# sd1_redraw.net
KiCad netlist of a schematic drawn in EAGLE
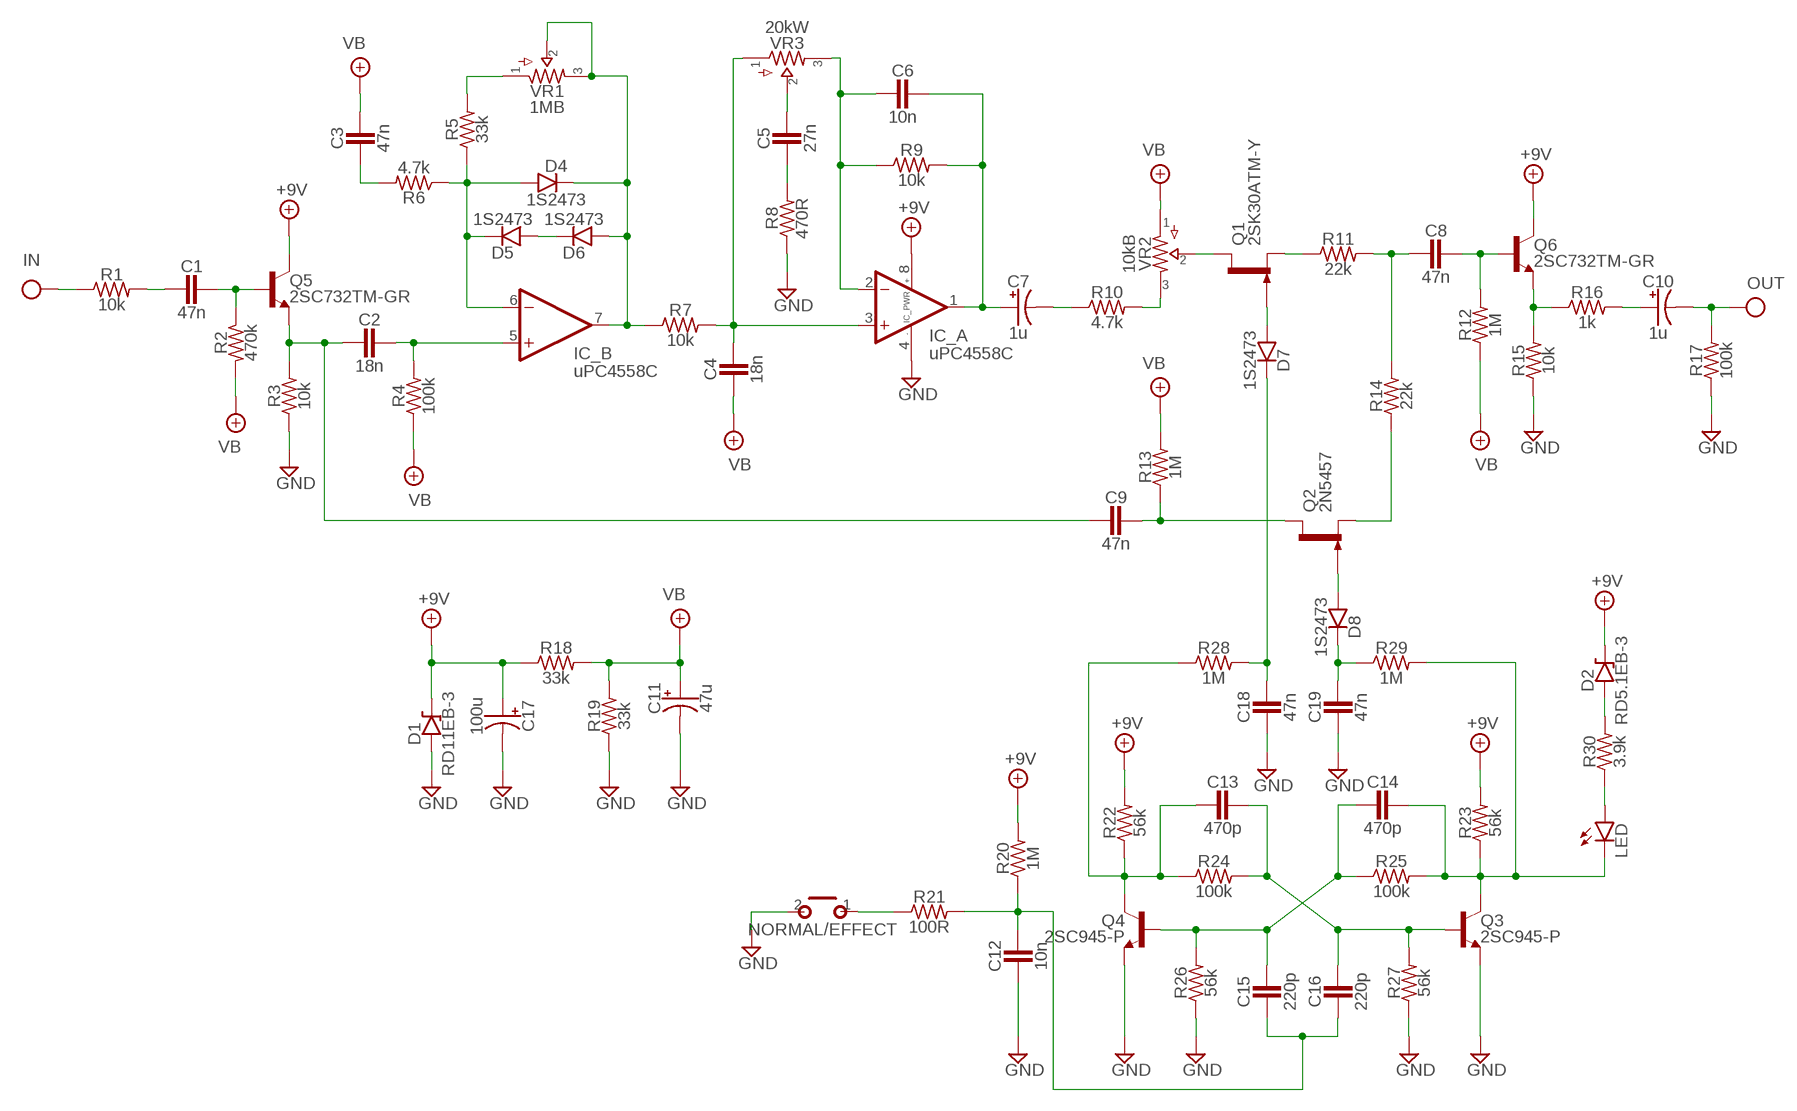
[diagram p0: schematic, sheet 1]

(export (version "E")
  (design (tool "Eeschema 10.0.6"))
  (components
    (comp (ref "C1")
      (value "47n")
      (footprint "eagle-import:BOX_SMALL")
      (libsource (lib "eagle-import") (part "CER/FILMBOX.1"))
    )
    (comp (ref "C2")
      (value "18n")
      (footprint "eagle-import:BOX_SMALL")
      (libsource (lib "eagle-import") (part "CER/FILMBOX.1"))
    )
    (comp (ref "C3")
      (value "47n")
      (footprint "eagle-import:BOX_SMALL")
      (libsource (lib "eagle-import") (part "CER/FILMBOX.1"))
    )
    (comp (ref "C4")
      (value "18n")
      (footprint "eagle-import:BOX_SMALL")
      (libsource (lib "eagle-import") (part "CER/FILMBOX.1"))
    )
    (comp (ref "C5")
      (value "27n")
      (footprint "eagle-import:BOX_SMALL")
      (libsource (lib "eagle-import") (part "CER/FILMBOX.1"))
    )
    (comp (ref "C6")
      (value "10n")
      (footprint "eagle-import:BOX_SMALL")
      (libsource (lib "eagle-import") (part "CER/FILMBOX.1"))
    )
    (comp (ref "C7")
      (value "1u")
      (footprint "eagle-import:040_020")
      (libsource (lib "eagle-import") (part "0400"))
    )
    (comp (ref "C8")
      (value "47n")
      (footprint "eagle-import:BOX_SMALL")
      (libsource (lib "eagle-import") (part "CER/FILMBOX.1"))
    )
    (comp (ref "C9")
      (value "47n")
      (footprint "eagle-import:BOX_SMALL")
      (libsource (lib "eagle-import") (part "CER/FILMBOX.1"))
    )
    (comp (ref "C10")
      (value "1u")
      (footprint "eagle-import:040_020")
      (libsource (lib "eagle-import") (part "0400"))
    )
    (comp (ref "C11")
      (value "47u")
      (footprint "eagle-import:040_020")
      (libsource (lib "eagle-import") (part "0400"))
    )
    (comp (ref "C12")
      (value "10n")
      (footprint "eagle-import:BOX_SMALL")
      (libsource (lib "eagle-import") (part "CER/FILMBOX.1"))
    )
    (comp (ref "C13")
      (value "470p")
      (footprint "eagle-import:BOX_SMALL")
      (libsource (lib "eagle-import") (part "CER/FILMBOX.1"))
    )
    (comp (ref "C14")
      (value "470p")
      (footprint "eagle-import:BOX_SMALL")
      (libsource (lib "eagle-import") (part "CER/FILMBOX.1"))
    )
    (comp (ref "C15")
      (value "220p")
      (footprint "eagle-import:BOX_SMALL")
      (libsource (lib "eagle-import") (part "CER/FILMBOX.1"))
    )
    (comp (ref "C16")
      (value "220p")
      (footprint "eagle-import:BOX_SMALL")
      (libsource (lib "eagle-import") (part "CER/FILMBOX.1"))
    )
    (comp (ref "C17")
      (value "100u")
      (footprint "eagle-import:040_020")
      (libsource (lib "eagle-import") (part "0400"))
    )
    (comp (ref "C18")
      (value "47n")
      (footprint "eagle-import:BOX_SMALL")
      (libsource (lib "eagle-import") (part "CER/FILMBOX.1"))
    )
    (comp (ref "C19")
      (value "47n")
      (footprint "eagle-import:BOX_SMALL")
      (libsource (lib "eagle-import") (part "CER/FILMBOX.1"))
    )
    (comp (ref "D1")
      (value "RD11EB-3")
      (footprint "eagle-import:DO41-2")
      (libsource (lib "eagle-import") (part "ZENER.2"))
    )
    (comp (ref "D2")
      (value "RD5.1EB-3")
      (footprint "eagle-import:DO41-2")
      (libsource (lib "eagle-import") (part "ZENER.2"))
    )
    (comp (ref "D4")
      (value "1S2473")
      (footprint "eagle-import:DO35-2")
      (libsource (lib "eagle-import") (part "DO35.2"))
    )
    (comp (ref "D5")
      (value "1S2473")
      (footprint "eagle-import:DO35-2")
      (libsource (lib "eagle-import") (part "DO35.2"))
    )
    (comp (ref "D6")
      (value "1S2473")
      (footprint "eagle-import:DO35-2")
      (libsource (lib "eagle-import") (part "DO35.2"))
    )
    (comp (ref "D7")
      (value "1S2473")
      (footprint "eagle-import:DO35-2")
      (libsource (lib "eagle-import") (part "DO35.2"))
    )
    (comp (ref "D8")
      (value "1S2473")
      (footprint "eagle-import:DO35-2")
      (libsource (lib "eagle-import") (part "DO35.2"))
    )
    (comp (ref "IC")
      (value "uPC4558C")
      (footprint "eagle-import:DIL0")
      (libsource (lib "eagle-import") (part "DUALTH"))
    )
    (comp (ref "LED")
      (value "SLP1358")
      (footprint "eagle-import:3MM_D")
      (libsource (lib "eagle-import") (part "LED"))
    )
    (comp (ref "NORMAL/EFFECT")
      (value "MOMENTARY")
      (footprint "eagle-import:SPST")
      (libsource (lib "eagle-import") (part "MOMENTARY"))
    )
    (comp (ref "Q1")
      (value "2SK30ATM-Y")
      (footprint "eagle-import:TO92-")
      (libsource (lib "eagle-import") (part "2N5457"))
    )
    (comp (ref "Q2")
      (value "2N5457")
      (footprint "eagle-import:TO92-")
      (libsource (lib "eagle-import") (part "2N5457"))
    )
    (comp (ref "Q3")
      (value "2SC945-P")
      (footprint "eagle-import:TO92-")
      (libsource (lib "eagle-import") (part "2SC828A"))
    )
    (comp (ref "Q4")
      (value "2SC945-P")
      (footprint "eagle-import:TO92-")
      (libsource (lib "eagle-import") (part "2SC828A"))
    )
    (comp (ref "Q5")
      (value "2SC732TM-GR")
      (footprint "eagle-import:TO92-")
      (libsource (lib "eagle-import") (part "2SC828A"))
    )
    (comp (ref "Q6")
      (value "2SC732TM-GR")
      (footprint "eagle-import:TO92-")
      (libsource (lib "eagle-import") (part "2SC828A"))
    )
    (comp (ref "R1")
      (value "10k")
      (footprint "eagle-import:R0207_3")
      (libsource (lib "eagle-import") (part "R_.3B"))
    )
    (comp (ref "R2")
      (value "470k")
      (footprint "eagle-import:R0207_3")
      (libsource (lib "eagle-import") (part "R_.3B"))
    )
    (comp (ref "R3")
      (value "10k")
      (footprint "eagle-import:R0207_3")
      (libsource (lib "eagle-import") (part "R_.3B"))
    )
    (comp (ref "R4")
      (value "100k")
      (footprint "eagle-import:R0207_3")
      (libsource (lib "eagle-import") (part "R_.3B"))
    )
    (comp (ref "R5")
      (value "33k")
      (footprint "eagle-import:R0207_3")
      (libsource (lib "eagle-import") (part "R_.3B"))
    )
    (comp (ref "R6")
      (value "4.7k")
      (footprint "eagle-import:R0207_3")
      (libsource (lib "eagle-import") (part "R_.3B"))
    )
    (comp (ref "R7")
      (value "10k")
      (footprint "eagle-import:R0207_3")
      (libsource (lib "eagle-import") (part "R_.3B"))
    )
    (comp (ref "R8")
      (value "470R")
      (footprint "eagle-import:R0207_3")
      (libsource (lib "eagle-import") (part "R_.3B"))
    )
    (comp (ref "R9")
      (value "10k")
      (footprint "eagle-import:R0207_3")
      (libsource (lib "eagle-import") (part "R_.3B"))
    )
    (comp (ref "R10")
      (value "4.7k")
      (footprint "eagle-import:R0207_3")
      (libsource (lib "eagle-import") (part "R_.3B"))
    )
    (comp (ref "R11")
      (value "22k")
      (footprint "eagle-import:R0207_3")
      (libsource (lib "eagle-import") (part "R_.3B"))
    )
    (comp (ref "R12")
      (value "1M")
      (footprint "eagle-import:R0207_3")
      (libsource (lib "eagle-import") (part "R_.3B"))
    )
    (comp (ref "R13")
      (value "1M")
      (footprint "eagle-import:R0207_3")
      (libsource (lib "eagle-import") (part "R_.3B"))
    )
    (comp (ref "R14")
      (value "22k")
      (footprint "eagle-import:R0207_3")
      (libsource (lib "eagle-import") (part "R_.3B"))
    )
    (comp (ref "R15")
      (value "10k")
      (footprint "eagle-import:R0207_3")
      (libsource (lib "eagle-import") (part "R_.3B"))
    )
    (comp (ref "R16")
      (value "1k")
      (footprint "eagle-import:R0207_3")
      (libsource (lib "eagle-import") (part "R_.3B"))
    )
    (comp (ref "R17")
      (value "100k")
      (footprint "eagle-import:R0207_3")
      (libsource (lib "eagle-import") (part "R_.3B"))
    )
    (comp (ref "R18")
      (value "33k")
      (footprint "eagle-import:R0207_3")
      (libsource (lib "eagle-import") (part "R_.3B"))
    )
    (comp (ref "R19")
      (value "33k")
      (footprint "eagle-import:R0207_3")
      (libsource (lib "eagle-import") (part "R_.3B"))
    )
    (comp (ref "R20")
      (value "1M")
      (footprint "eagle-import:R0207_3")
      (libsource (lib "eagle-import") (part "R_.3B"))
    )
    (comp (ref "R21")
      (value "100R")
      (footprint "eagle-import:R0207_3")
      (libsource (lib "eagle-import") (part "R_.3B"))
    )
    (comp (ref "R22")
      (value "56k")
      (footprint "eagle-import:R0207_3")
      (libsource (lib "eagle-import") (part "R_.3B"))
    )
    (comp (ref "R23")
      (value "56k")
      (footprint "eagle-import:R0207_3")
      (libsource (lib "eagle-import") (part "R_.3B"))
    )
    (comp (ref "R24")
      (value "100k")
      (footprint "eagle-import:R0207_3")
      (libsource (lib "eagle-import") (part "R_.3B"))
    )
    (comp (ref "R25")
      (value "100k")
      (footprint "eagle-import:R0207_3")
      (libsource (lib "eagle-import") (part "R_.3B"))
    )
    (comp (ref "R26")
      (value "56k")
      (footprint "eagle-import:R0207_3")
      (libsource (lib "eagle-import") (part "R_.3B"))
    )
    (comp (ref "R27")
      (value "56k")
      (footprint "eagle-import:R0207_3")
      (libsource (lib "eagle-import") (part "R_.3B"))
    )
    (comp (ref "R28")
      (value "1M")
      (footprint "eagle-import:R0207_3")
      (libsource (lib "eagle-import") (part "R_.3B"))
    )
    (comp (ref "R29")
      (value "1M")
      (footprint "eagle-import:R0207_3")
      (libsource (lib "eagle-import") (part "R_.3B"))
    )
    (comp (ref "R30")
      (value "3.9k")
      (footprint "eagle-import:R0207_3")
      (libsource (lib "eagle-import") (part "R_.3B"))
    )
    (comp (ref "VR1")
      (value "1MB")
      (footprint "eagle-import:16MM")
      (libsource (lib "eagle-import") (part "POTS16MM"))
    )
    (comp (ref "VR2")
      (value "10kB")
      (footprint "eagle-import:16MM")
      (libsource (lib "eagle-import") (part "POTS16MM"))
    )
    (comp (ref "VR3")
      (value "20kW")
      (footprint "eagle-import:16MM")
      (libsource (lib "eagle-import") (part "POTS16MM"))
    )
  )
  (nets
    (net (code "1") (name "+9V") (class "Default")
      (node (ref "C17") (pin "+") (pinfunction "+_+") (pintype "passive"))
      (node (ref "D1") (pin "C") (pinfunction "C_C") (pintype "passive"))
      (node (ref "D2") (pin "C") (pinfunction "C_C") (pintype "passive"))
      (node (ref "IC") (pin "8") (pinfunction "V+_8") (pintype "power_in"))
      (node (ref "Q5") (pin "2") (pinfunction "C_2") (pintype "passive"))
      (node (ref "Q6") (pin "2") (pinfunction "C_2") (pintype "passive"))
      (node (ref "R18") (pin "1") (pinfunction "1_1") (pintype "passive"))
      (node (ref "R20") (pin "2") (pinfunction "2_2") (pintype "passive"))
      (node (ref "R22") (pin "2") (pinfunction "2_2") (pintype "passive"))
      (node (ref "R23") (pin "2") (pinfunction "2_2") (pintype "passive"))
    )
    (net (code "2") (name "GND") (class "Default")
      (node (ref "C11") (pin "-") (pinfunction "-_-") (pintype "passive"))
      (node (ref "C12") (pin "2") (pinfunction "2_2") (pintype "passive"))
      (node (ref "C17") (pin "-") (pinfunction "-_-") (pintype "passive"))
      (node (ref "C18") (pin "2") (pinfunction "2_2") (pintype "passive"))
      (node (ref "C19") (pin "2") (pinfunction "2_2") (pintype "passive"))
      (node (ref "D1") (pin "A") (pinfunction "A_A") (pintype "passive"))
      (node (ref "IC") (pin "4") (pinfunction "V-_4") (pintype "power_in"))
      (node (ref "NORMAL/EFFECT") (pin "2") (pinfunction "S_2") (pintype "passive"))
      (node (ref "Q3") (pin "3") (pinfunction "E_3") (pintype "passive"))
      (node (ref "Q4") (pin "3") (pinfunction "E_3") (pintype "passive"))
      (node (ref "R15") (pin "1") (pinfunction "1_1") (pintype "passive"))
      (node (ref "R17") (pin "1") (pinfunction "1_1") (pintype "passive"))
      (node (ref "R19") (pin "1") (pinfunction "1_1") (pintype "passive"))
      (node (ref "R26") (pin "1") (pinfunction "1_1") (pintype "passive"))
      (node (ref "R27") (pin "1") (pinfunction "1_1") (pintype "passive"))
      (node (ref "R3") (pin "1") (pinfunction "1_1") (pintype "passive"))
      (node (ref "R8") (pin "1") (pinfunction "1_1") (pintype "passive"))
    )
    (net (code "3") (name "IN") (class "Default")
      (node (ref "R1") (pin "1") (pinfunction "1_1") (pintype "passive"))
    )
    (net (code "4") (name "Net-(C1-Pad2)") (class "Default")
      (node (ref "C1") (pin "2") (pinfunction "2_2") (pintype "passive"))
      (node (ref "R1") (pin "2") (pinfunction "2_2") (pintype "passive"))
    )
    (net (code "5") (name "Net-(C3-Pad2)") (class "Default")
      (node (ref "C3") (pin "2") (pinfunction "2_2") (pintype "passive"))
      (node (ref "R6") (pin "2") (pinfunction "2_2") (pintype "passive"))
    )
    (net (code "6") (name "Net-(C5-Pad1)") (class "Default")
      (node (ref "C5") (pin "1") (pinfunction "1_1") (pintype "passive"))
      (node (ref "VR3") (pin "2") (pinfunction "2_2") (pintype "passive"))
    )
    (net (code "7") (name "Net-(C5-Pad2)") (class "Default")
      (node (ref "C5") (pin "2") (pinfunction "2_2") (pintype "passive"))
      (node (ref "R8") (pin "2") (pinfunction "2_2") (pintype "passive"))
    )
    (net (code "8") (name "Net-(C7-Pad-)") (class "Default")
      (node (ref "C7") (pin "-") (pinfunction "-_-") (pintype "passive"))
      (node (ref "R10") (pin "1") (pinfunction "1_1") (pintype "passive"))
    )
    (net (code "9") (name "Net-(C8-Pad2)") (class "Default")
      (node (ref "C8") (pin "2") (pinfunction "2_2") (pintype "passive"))
      (node (ref "R11") (pin "2") (pinfunction "2_2") (pintype "passive"))
      (node (ref "R14") (pin "2") (pinfunction "2_2") (pintype "passive"))
    )
    (net (code "10") (name "Net-(C10-Pad+)") (class "Default")
      (node (ref "C10") (pin "+") (pinfunction "+_+") (pintype "passive"))
      (node (ref "R16") (pin "2") (pinfunction "2_2") (pintype "passive"))
    )
    (net (code "11") (name "Net-(C12-Pad1)") (class "Default")
      (node (ref "C12") (pin "1") (pinfunction "1_1") (pintype "passive"))
      (node (ref "C15") (pin "2") (pinfunction "2_2") (pintype "passive"))
      (node (ref "C16") (pin "2") (pinfunction "2_2") (pintype "passive"))
      (node (ref "R20") (pin "1") (pinfunction "1_1") (pintype "passive"))
      (node (ref "R21") (pin "2") (pinfunction "2_2") (pintype "passive"))
    )
    (net (code "12") (name "Net-(C18-Pad1)") (class "Default")
      (node (ref "C18") (pin "1") (pinfunction "1_1") (pintype "passive"))
      (node (ref "D7") (pin "C") (pinfunction "C_C") (pintype "passive"))
      (node (ref "R28") (pin "2") (pinfunction "2_2") (pintype "passive"))
    )
    (net (code "13") (name "Net-(C19-Pad1)") (class "Default")
      (node (ref "C19") (pin "1") (pinfunction "1_1") (pintype "passive"))
      (node (ref "D8") (pin "C") (pinfunction "C_C") (pintype "passive"))
      (node (ref "R29") (pin "1") (pinfunction "1_1") (pintype "passive"))
    )
    (net (code "14") (name "Net-(D2-PadA)") (class "Default")
      (node (ref "D2") (pin "A") (pinfunction "A_A") (pintype "passive"))
      (node (ref "R30") (pin "2") (pinfunction "2_2") (pintype "passive"))
    )
    (net (code "15") (name "Net-(D5-PadA)") (class "Default")
      (node (ref "D5") (pin "A") (pinfunction "A_A") (pintype "passive"))
      (node (ref "D6") (pin "C") (pinfunction "C_C") (pintype "passive"))
    )
    (net (code "16") (name "Net-(ICA-+IN)") (class "Default")
      (node (ref "C4") (pin "1") (pinfunction "1_1") (pintype "passive"))
      (node (ref "IC") (pin "3") (pinfunction "+IN_3") (pintype "input"))
      (node (ref "R7") (pin "2") (pinfunction "2_2") (pintype "passive"))
      (node (ref "VR3") (pin "1") (pinfunction "1_1") (pintype "passive"))
    )
    (net (code "17") (name "Net-(ICA--IN)") (class "Default")
      (node (ref "C6") (pin "2") (pinfunction "2_2") (pintype "passive"))
      (node (ref "IC") (pin "2") (pinfunction "-IN_2") (pintype "input"))
      (node (ref "R9") (pin "1") (pinfunction "1_1") (pintype "passive"))
      (node (ref "VR3") (pin "3") (pinfunction "3_3") (pintype "passive"))
    )
    (net (code "18") (name "Net-(ICA-OUT)") (class "Default")
      (node (ref "C6") (pin "1") (pinfunction "1_1") (pintype "passive"))
      (node (ref "C7") (pin "+") (pinfunction "+_+") (pintype "passive"))
      (node (ref "IC") (pin "1") (pinfunction "OUT_1") (pintype "output"))
      (node (ref "R9") (pin "2") (pinfunction "2_2") (pintype "passive"))
    )
    (net (code "19") (name "Net-(ICB-+IN)") (class "Default")
      (node (ref "C2") (pin "1") (pinfunction "1_1") (pintype "passive"))
      (node (ref "IC") (pin "5") (pinfunction "+IN_5") (pintype "input"))
      (node (ref "R4") (pin "2") (pinfunction "2_2") (pintype "passive"))
    )
    (net (code "20") (name "Net-(ICB--IN)") (class "Default")
      (node (ref "D4") (pin "A") (pinfunction "A_A") (pintype "passive"))
      (node (ref "D5") (pin "C") (pinfunction "C_C") (pintype "passive"))
      (node (ref "IC") (pin "6") (pinfunction "-IN_6") (pintype "input"))
      (node (ref "R5") (pin "1") (pinfunction "1_1") (pintype "passive"))
      (node (ref "R6") (pin "1") (pinfunction "1_1") (pintype "passive"))
    )
    (net (code "21") (name "Net-(ICB-OUT)") (class "Default")
      (node (ref "D4") (pin "C") (pinfunction "C_C") (pintype "passive"))
      (node (ref "D6") (pin "A") (pinfunction "A_A") (pintype "passive"))
      (node (ref "IC") (pin "7") (pinfunction "OUT_7") (pintype "output"))
      (node (ref "R7") (pin "1") (pinfunction "1_1") (pintype "passive"))
      (node (ref "VR1") (pin "2") (pinfunction "2_2") (pintype "passive"))
      (node (ref "VR1") (pin "3") (pinfunction "3_3") (pintype "passive"))
    )
    (net (code "22") (name "Net-(LED-A)") (class "Default")
      (node (ref "LED") (pin "ANODE") (pinfunction "A_ANODE") (pintype "passive"))
      (node (ref "R30") (pin "1") (pinfunction "1_1") (pintype "passive"))
    )
    (net (code "23") (name "Net-(LED-C)") (class "Default")
      (node (ref "C14") (pin "1") (pinfunction "1_1") (pintype "passive"))
      (node (ref "LED") (pin "P$1") (pinfunction "C_P$1") (pintype "passive"))
      (node (ref "Q3") (pin "2") (pinfunction "C_2") (pintype "passive"))
      (node (ref "R23") (pin "1") (pinfunction "1_1") (pintype "passive"))
      (node (ref "R25") (pin "2") (pinfunction "2_2") (pintype "passive"))
      (node (ref "R29") (pin "2") (pinfunction "2_2") (pintype "passive"))
    )
    (net (code "24") (name "Net-(NORMAL/EFFECT-P)") (class "Default")
      (node (ref "NORMAL/EFFECT") (pin "1") (pinfunction "P_1") (pintype "passive"))
      (node (ref "R21") (pin "1") (pinfunction "1_1") (pintype "passive"))
    )
    (net (code "25") (name "Net-(Q1-D)") (class "Default")
      (node (ref "Q1") (pin "3") (pinfunction "D_3") (pintype "passive"))
      (node (ref "VR2") (pin "2") (pinfunction "2_2") (pintype "passive"))
    )
    (net (code "26") (name "Net-(Q1-G)") (class "Default")
      (node (ref "D7") (pin "A") (pinfunction "A_A") (pintype "passive"))
      (node (ref "Q1") (pin "1") (pinfunction "G_1") (pintype "passive"))
    )
    (net (code "27") (name "Net-(Q1-S)") (class "Default")
      (node (ref "Q1") (pin "2") (pinfunction "S_2") (pintype "passive"))
      (node (ref "R11") (pin "1") (pinfunction "1_1") (pintype "passive"))
    )
    (net (code "28") (name "Net-(Q2-D)") (class "Default")
      (node (ref "C9") (pin "1") (pinfunction "1_1") (pintype "passive"))
      (node (ref "Q2") (pin "3") (pinfunction "D_3") (pintype "passive"))
      (node (ref "R13") (pin "1") (pinfunction "1_1") (pintype "passive"))
    )
    (net (code "29") (name "Net-(Q2-G)") (class "Default")
      (node (ref "D8") (pin "A") (pinfunction "A_A") (pintype "passive"))
      (node (ref "Q2") (pin "1") (pinfunction "G_1") (pintype "passive"))
    )
    (net (code "30") (name "Net-(Q2-S)") (class "Default")
      (node (ref "Q2") (pin "2") (pinfunction "S_2") (pintype "passive"))
      (node (ref "R14") (pin "1") (pinfunction "1_1") (pintype "passive"))
    )
    (net (code "31") (name "Net-(Q3-B)") (class "Default")
      (node (ref "C13") (pin "1") (pinfunction "1_1") (pintype "passive"))
      (node (ref "C16") (pin "1") (pinfunction "1_1") (pintype "passive"))
      (node (ref "Q3") (pin "1") (pinfunction "B_1") (pintype "passive"))
      (node (ref "R24") (pin "2") (pinfunction "2_2") (pintype "passive"))
      (node (ref "R27") (pin "2") (pinfunction "2_2") (pintype "passive"))
    )
    (net (code "32") (name "Net-(Q4-B)") (class "Default")
      (node (ref "C14") (pin "2") (pinfunction "2_2") (pintype "passive"))
      (node (ref "C15") (pin "1") (pinfunction "1_1") (pintype "passive"))
      (node (ref "Q4") (pin "1") (pinfunction "B_1") (pintype "passive"))
      (node (ref "R25") (pin "1") (pinfunction "1_1") (pintype "passive"))
      (node (ref "R26") (pin "2") (pinfunction "2_2") (pintype "passive"))
    )
    (net (code "33") (name "Net-(Q4-C)") (class "Default")
      (node (ref "C13") (pin "2") (pinfunction "2_2") (pintype "passive"))
      (node (ref "Q4") (pin "2") (pinfunction "C_2") (pintype "passive"))
      (node (ref "R22") (pin "1") (pinfunction "1_1") (pintype "passive"))
      (node (ref "R24") (pin "1") (pinfunction "1_1") (pintype "passive"))
      (node (ref "R28") (pin "1") (pinfunction "1_1") (pintype "passive"))
    )
    (net (code "34") (name "Net-(Q5-B)") (class "Default")
      (node (ref "C1") (pin "1") (pinfunction "1_1") (pintype "passive"))
      (node (ref "Q5") (pin "1") (pinfunction "B_1") (pintype "passive"))
      (node (ref "R2") (pin "1") (pinfunction "1_1") (pintype "passive"))
    )
    (net (code "35") (name "Net-(Q5-E)") (class "Default")
      (node (ref "C2") (pin "2") (pinfunction "2_2") (pintype "passive"))
      (node (ref "C9") (pin "2") (pinfunction "2_2") (pintype "passive"))
      (node (ref "Q5") (pin "3") (pinfunction "E_3") (pintype "passive"))
      (node (ref "R3") (pin "2") (pinfunction "2_2") (pintype "passive"))
    )
    (net (code "36") (name "Net-(Q6-B)") (class "Default")
      (node (ref "C8") (pin "1") (pinfunction "1_1") (pintype "passive"))
      (node (ref "Q6") (pin "1") (pinfunction "B_1") (pintype "passive"))
      (node (ref "R12") (pin "2") (pinfunction "2_2") (pintype "passive"))
    )
    (net (code "37") (name "Net-(Q6-E)") (class "Default")
      (node (ref "Q6") (pin "3") (pinfunction "E_3") (pintype "passive"))
      (node (ref "R15") (pin "2") (pinfunction "2_2") (pintype "passive"))
      (node (ref "R16") (pin "1") (pinfunction "1_1") (pintype "passive"))
    )
    (net (code "38") (name "Net-(R5-Pad2)") (class "Default")
      (node (ref "R5") (pin "2") (pinfunction "2_2") (pintype "passive"))
      (node (ref "VR1") (pin "1") (pinfunction "1_1") (pintype "passive"))
    )
    (net (code "39") (name "Net-(R10-Pad2)") (class "Default")
      (node (ref "R10") (pin "2") (pinfunction "2_2") (pintype "passive"))
      (node (ref "VR2") (pin "3") (pinfunction "3_3") (pintype "passive"))
    )
    (net (code "40") (name "OUT") (class "Default")
      (node (ref "C10") (pin "-") (pinfunction "-_-") (pintype "passive"))
      (node (ref "R17") (pin "2") (pinfunction "2_2") (pintype "passive"))
    )
    (net (code "41") (name "VB") (class "Default")
      (node (ref "C11") (pin "+") (pinfunction "+_+") (pintype "passive"))
      (node (ref "C3") (pin "1") (pinfunction "1_1") (pintype "passive"))
      (node (ref "C4") (pin "2") (pinfunction "2_2") (pintype "passive"))
      (node (ref "R12") (pin "1") (pinfunction "1_1") (pintype "passive"))
      (node (ref "R13") (pin "2") (pinfunction "2_2") (pintype "passive"))
      (node (ref "R18") (pin "2") (pinfunction "2_2") (pintype "passive"))
      (node (ref "R19") (pin "2") (pinfunction "2_2") (pintype "passive"))
      (node (ref "R2") (pin "2") (pinfunction "2_2") (pintype "passive"))
      (node (ref "R4") (pin "1") (pinfunction "1_1") (pintype "passive"))
      (node (ref "VR2") (pin "1") (pinfunction "1_1") (pintype "passive"))
    )
  )
)
